# dc_motor.net
KiCad netlist of a schematic drawn in Altium Designer
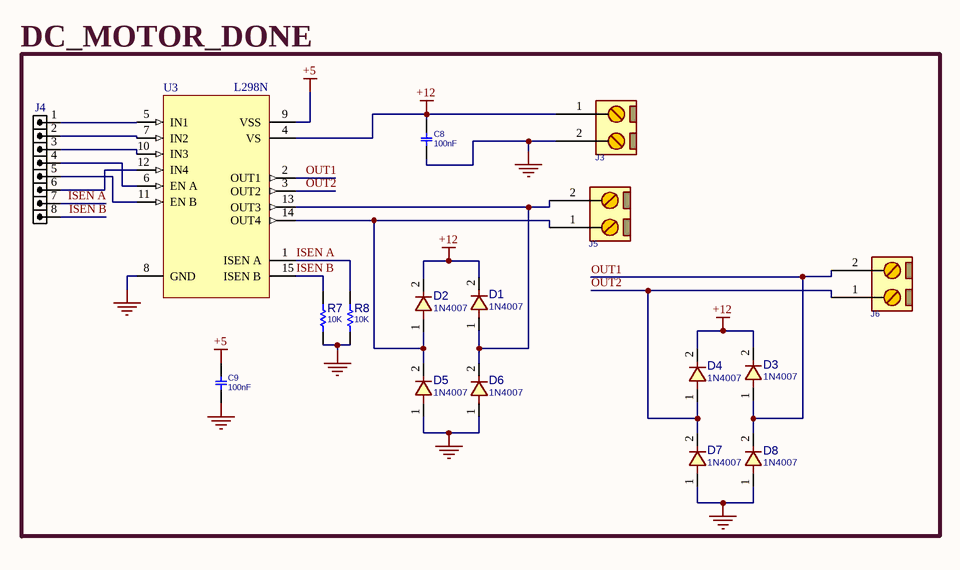
[diagram p0: dc_motor.SchDoc]

(export (version "E")
  (design (tool "Eeschema 10.0.6"))
  (components
    (comp (ref "C8")
      (value "100nF")
      (footprint "C_CER_D3")
      (description "CAP, THD, CER MULTI LAYER,")
      (fields (field (name "MANF_P#") "MANF_PART#") (field (name "MANF") "MANF"))
      (libsource (lib "CapCer_passive") (part "CAP_THD_CERML"))
    )
    (comp (ref "C9")
      (value "100nF")
      (footprint "C_CER_D3")
      (description "CAP, THD, CER MULTI LAYER,")
      (fields (field (name "MANF_P#") "MANF_PART#") (field (name "MANF") "MANF"))
      (libsource (lib "CapCer_passive") (part "CAP_THD_CERML"))
    )
    (comp (ref "D1")
      (value "1N4007")
      (footprint "D_AX04_DO41")
      (description "DIODE, GENERAL PURPOSE, 1000V/1A")
      (fields (field (name "MANF") "Kingtronics") (field (name "MANF_P#") "M7"))
      (libsource (lib "diode") (part "DIODE_SMD_1N4007"))
    )
    (comp (ref "D2")
      (value "1N4007")
      (footprint "D_AX04_DO41")
      (description "DIODE, GENERAL PURPOSE, 1000V/1A")
      (fields (field (name "MANF") "Kingtronics") (field (name "MANF_P#") "M7"))
      (libsource (lib "diode") (part "DIODE_SMD_1N4007"))
    )
    (comp (ref "D3")
      (value "1N4007")
      (footprint "D_AX04_DO41")
      (description "DIODE, GENERAL PURPOSE, 1000V/1A")
      (fields (field (name "MANF") "Kingtronics") (field (name "MANF_P#") "M7"))
      (libsource (lib "diode") (part "DIODE_SMD_1N4007"))
    )
    (comp (ref "D4")
      (value "1N4007")
      (footprint "D_AX04_DO41")
      (description "DIODE, GENERAL PURPOSE, 1000V/1A")
      (fields (field (name "MANF") "Kingtronics") (field (name "MANF_P#") "M7"))
      (libsource (lib "diode") (part "DIODE_SMD_1N4007"))
    )
    (comp (ref "D5")
      (value "1N4007")
      (footprint "D_AX04_DO41")
      (description "DIODE, GENERAL PURPOSE, 1000V/1A")
      (fields (field (name "MANF") "Kingtronics") (field (name "MANF_P#") "M7"))
      (libsource (lib "diode") (part "DIODE_SMD_1N4007"))
    )
    (comp (ref "D6")
      (value "1N4007")
      (footprint "D_AX04_DO41")
      (description "DIODE, GENERAL PURPOSE, 1000V/1A")
      (fields (field (name "MANF") "Kingtronics") (field (name "MANF_P#") "M7"))
      (libsource (lib "diode") (part "DIODE_SMD_1N4007"))
    )
    (comp (ref "D7")
      (value "1N4007")
      (footprint "D_AX04_DO41")
      (description "DIODE, GENERAL PURPOSE, 1000V/1A")
      (fields (field (name "MANF") "Kingtronics") (field (name "MANF_P#") "M7"))
      (libsource (lib "diode") (part "DIODE_SMD_1N4007"))
    )
    (comp (ref "D8")
      (value "1N4007")
      (footprint "D_AX04_DO41")
      (description "DIODE, GENERAL PURPOSE, 1000V/1A")
      (fields (field (name "MANF") "Kingtronics") (field (name "MANF_P#") "M7"))
      (libsource (lib "diode") (part "DIODE_SMD_1N4007"))
    )
    (comp (ref "J3")
      (value "CONN_TB2")
      (footprint "TBG_2")
      (description "CONN, TERMINAL BLOCK, 5.08mm pitch")
      (libsource (lib "") (part "CONN_TB2_1"))
    )
    (comp (ref "J4")
      (value "HDR1X8")
      (footprint "HDR_M_1X8")
      (description "CONN, HEADER, Male, pitch: 2.54mm, 8POS")
      (libsource (lib "conn_header_2.54mm_st") (part "HDR_M_1X8"))
    )
    (comp (ref "J5")
      (value "CONN_TB2")
      (footprint "TBG_2")
      (description "CONN, TERMINAL BLOCK, 5.08mm pitch")
      (libsource (lib "conn_power_terminalB") (part "CONN_TB2"))
    )
    (comp (ref "J6")
      (value "CONN_TB2")
      (footprint "TBG_2")
      (description "CONN, TERMINAL BLOCK, 5.08mm pitch")
      (libsource (lib "conn_power_terminalB") (part "CONN_TB2"))
    )
    (comp (ref "R7")
      (value "10K")
      (footprint "R025W_AX04")
      (description "RESISTOR, THD")
      (fields (field (name "MANF_P#") "RK73H1ETTP4701F") (field (name "MANF") "KOA SPEER"))
      (libsource (lib "passive_thd") (part "RES_THD"))
    )
    (comp (ref "R8")
      (value "10K")
      (footprint "R025W_AX04")
      (description "RESISTOR, THD")
      (fields (field (name "MANF_P#") "RK73H1ETTP4701F") (field (name "MANF") "KOA SPEER"))
      (libsource (lib "passive_thd") (part "RES_THD"))
    )
    (comp (ref "U3")
      (value "L298N")
      (footprint "MULTIWATT_15V")
      (description "CREATED BY J")
      (libsource (lib "AvrDevelopmentBoard") (part "L298N"))
    )
  )
  (nets
    (net (code "1") (name "+5") (class "Default")
      (node (ref "C9") (pin "2") (pinfunction "2_2") (pintype "passive"))
      (node (ref "U3") (pin "9") (pinfunction "VSS_9") (pintype "passive"))
    )
    (net (code "2") (name "+12") (class "Default")
      (node (ref "C8") (pin "2") (pinfunction "2_2") (pintype "passive"))
      (node (ref "D1") (pin "2") (pinfunction "2_2") (pintype "passive"))
      (node (ref "D2") (pin "2") (pinfunction "2_2") (pintype "passive"))
      (node (ref "D3") (pin "2") (pinfunction "2_2") (pintype "passive"))
      (node (ref "D4") (pin "2") (pinfunction "2_2") (pintype "passive"))
      (node (ref "J3") (pin "1") (pinfunction "1_1") (pintype "passive"))
      (node (ref "U3") (pin "4") (pinfunction "VS_4") (pintype "passive"))
    )
    (net (code "3") (name "/ISEN A") (class "Default")
      (node (ref "J4") (pin "7") (pinfunction "7_7") (pintype "passive"))
      (node (ref "R8") (pin "1") (pinfunction "1_1") (pintype "passive"))
      (node (ref "U3") (pin "1") (pinfunction "ISEN_A_1") (pintype "passive"))
    )
    (net (code "4") (name "/ISEN B") (class "Default")
      (node (ref "J4") (pin "8") (pinfunction "8_8") (pintype "passive"))
      (node (ref "R7") (pin "1") (pinfunction "1_1") (pintype "passive"))
      (node (ref "U3") (pin "15") (pinfunction "ISEN_B_15") (pintype "passive"))
    )
    (net (code "5") (name "/OUT1") (class "Default")
      (node (ref "D3") (pin "1") (pinfunction "1_1") (pintype "passive"))
      (node (ref "D8") (pin "2") (pinfunction "2_2") (pintype "passive"))
      (node (ref "J6") (pin "2") (pinfunction "2_2") (pintype "passive"))
      (node (ref "U3") (pin "2") (pinfunction "OUT1_2") (pintype "output"))
    )
    (net (code "6") (name "/OUT2") (class "Default")
      (node (ref "D4") (pin "1") (pinfunction "1_1") (pintype "passive"))
      (node (ref "D7") (pin "2") (pinfunction "2_2") (pintype "passive"))
      (node (ref "J6") (pin "1") (pinfunction "1_1") (pintype "passive"))
      (node (ref "U3") (pin "3") (pinfunction "OUT2_3") (pintype "output"))
    )
    (net (code "7") (name "GND") (class "Default")
      (node (ref "C8") (pin "1") (pinfunction "1_1") (pintype "passive"))
      (node (ref "C9") (pin "1") (pinfunction "1_1") (pintype "passive"))
      (node (ref "D5") (pin "1") (pinfunction "1_1") (pintype "passive"))
      (node (ref "D6") (pin "1") (pinfunction "1_1") (pintype "passive"))
      (node (ref "D7") (pin "1") (pinfunction "1_1") (pintype "passive"))
      (node (ref "D8") (pin "1") (pinfunction "1_1") (pintype "passive"))
      (node (ref "J3") (pin "2") (pinfunction "2_2") (pintype "passive"))
      (node (ref "R7") (pin "2") (pinfunction "2_2") (pintype "passive"))
      (node (ref "R8") (pin "2") (pinfunction "2_2") (pintype "passive"))
      (node (ref "U3") (pin "8") (pinfunction "GND_8") (pintype "passive"))
    )
    (net (code "8") (name "Net-(U3-EN_A)") (class "Default")
      (node (ref "J4") (pin "4") (pinfunction "4_4") (pintype "passive"))
      (node (ref "U3") (pin "6") (pinfunction "EN_A_6") (pintype "input"))
    )
    (net (code "9") (name "Net-(U3-EN_B)") (class "Default")
      (node (ref "J4") (pin "5") (pinfunction "5_5") (pintype "passive"))
      (node (ref "U3") (pin "11") (pinfunction "EN_B_11") (pintype "input"))
    )
    (net (code "10") (name "Net-(U3-IN1)") (class "Default")
      (node (ref "J4") (pin "1") (pinfunction "1_1") (pintype "passive"))
      (node (ref "U3") (pin "5") (pinfunction "IN1_5") (pintype "input"))
    )
    (net (code "11") (name "Net-(U3-IN2)") (class "Default")
      (node (ref "J4") (pin "2") (pinfunction "2_2") (pintype "passive"))
      (node (ref "U3") (pin "7") (pinfunction "IN2_7") (pintype "input"))
    )
    (net (code "12") (name "Net-(U3-IN3)") (class "Default")
      (node (ref "J4") (pin "3") (pinfunction "3_3") (pintype "passive"))
      (node (ref "U3") (pin "10") (pinfunction "IN3_10") (pintype "input"))
    )
    (net (code "13") (name "Net-(U3-IN4)") (class "Default")
      (node (ref "J4") (pin "6") (pinfunction "6_6") (pintype "passive"))
      (node (ref "U3") (pin "12") (pinfunction "IN4_12") (pintype "input"))
    )
    (net (code "14") (name "Net-(U3-OUT3)") (class "Default")
      (node (ref "D1") (pin "1") (pinfunction "1_1") (pintype "passive"))
      (node (ref "D6") (pin "2") (pinfunction "2_2") (pintype "passive"))
      (node (ref "J5") (pin "2") (pinfunction "2_2") (pintype "passive"))
      (node (ref "U3") (pin "13") (pinfunction "OUT3_13") (pintype "output"))
    )
    (net (code "15") (name "Net-(U3-OUT4)") (class "Default")
      (node (ref "D2") (pin "1") (pinfunction "1_1") (pintype "passive"))
      (node (ref "D5") (pin "2") (pinfunction "2_2") (pintype "passive"))
      (node (ref "J5") (pin "1") (pinfunction "1_1") (pintype "passive"))
      (node (ref "U3") (pin "14") (pinfunction "OUT4_14") (pintype "output"))
    )
  )
)
